# Rain_Sensor.net
KiCad netlist of a schematic drawn in EasyEDA Pro
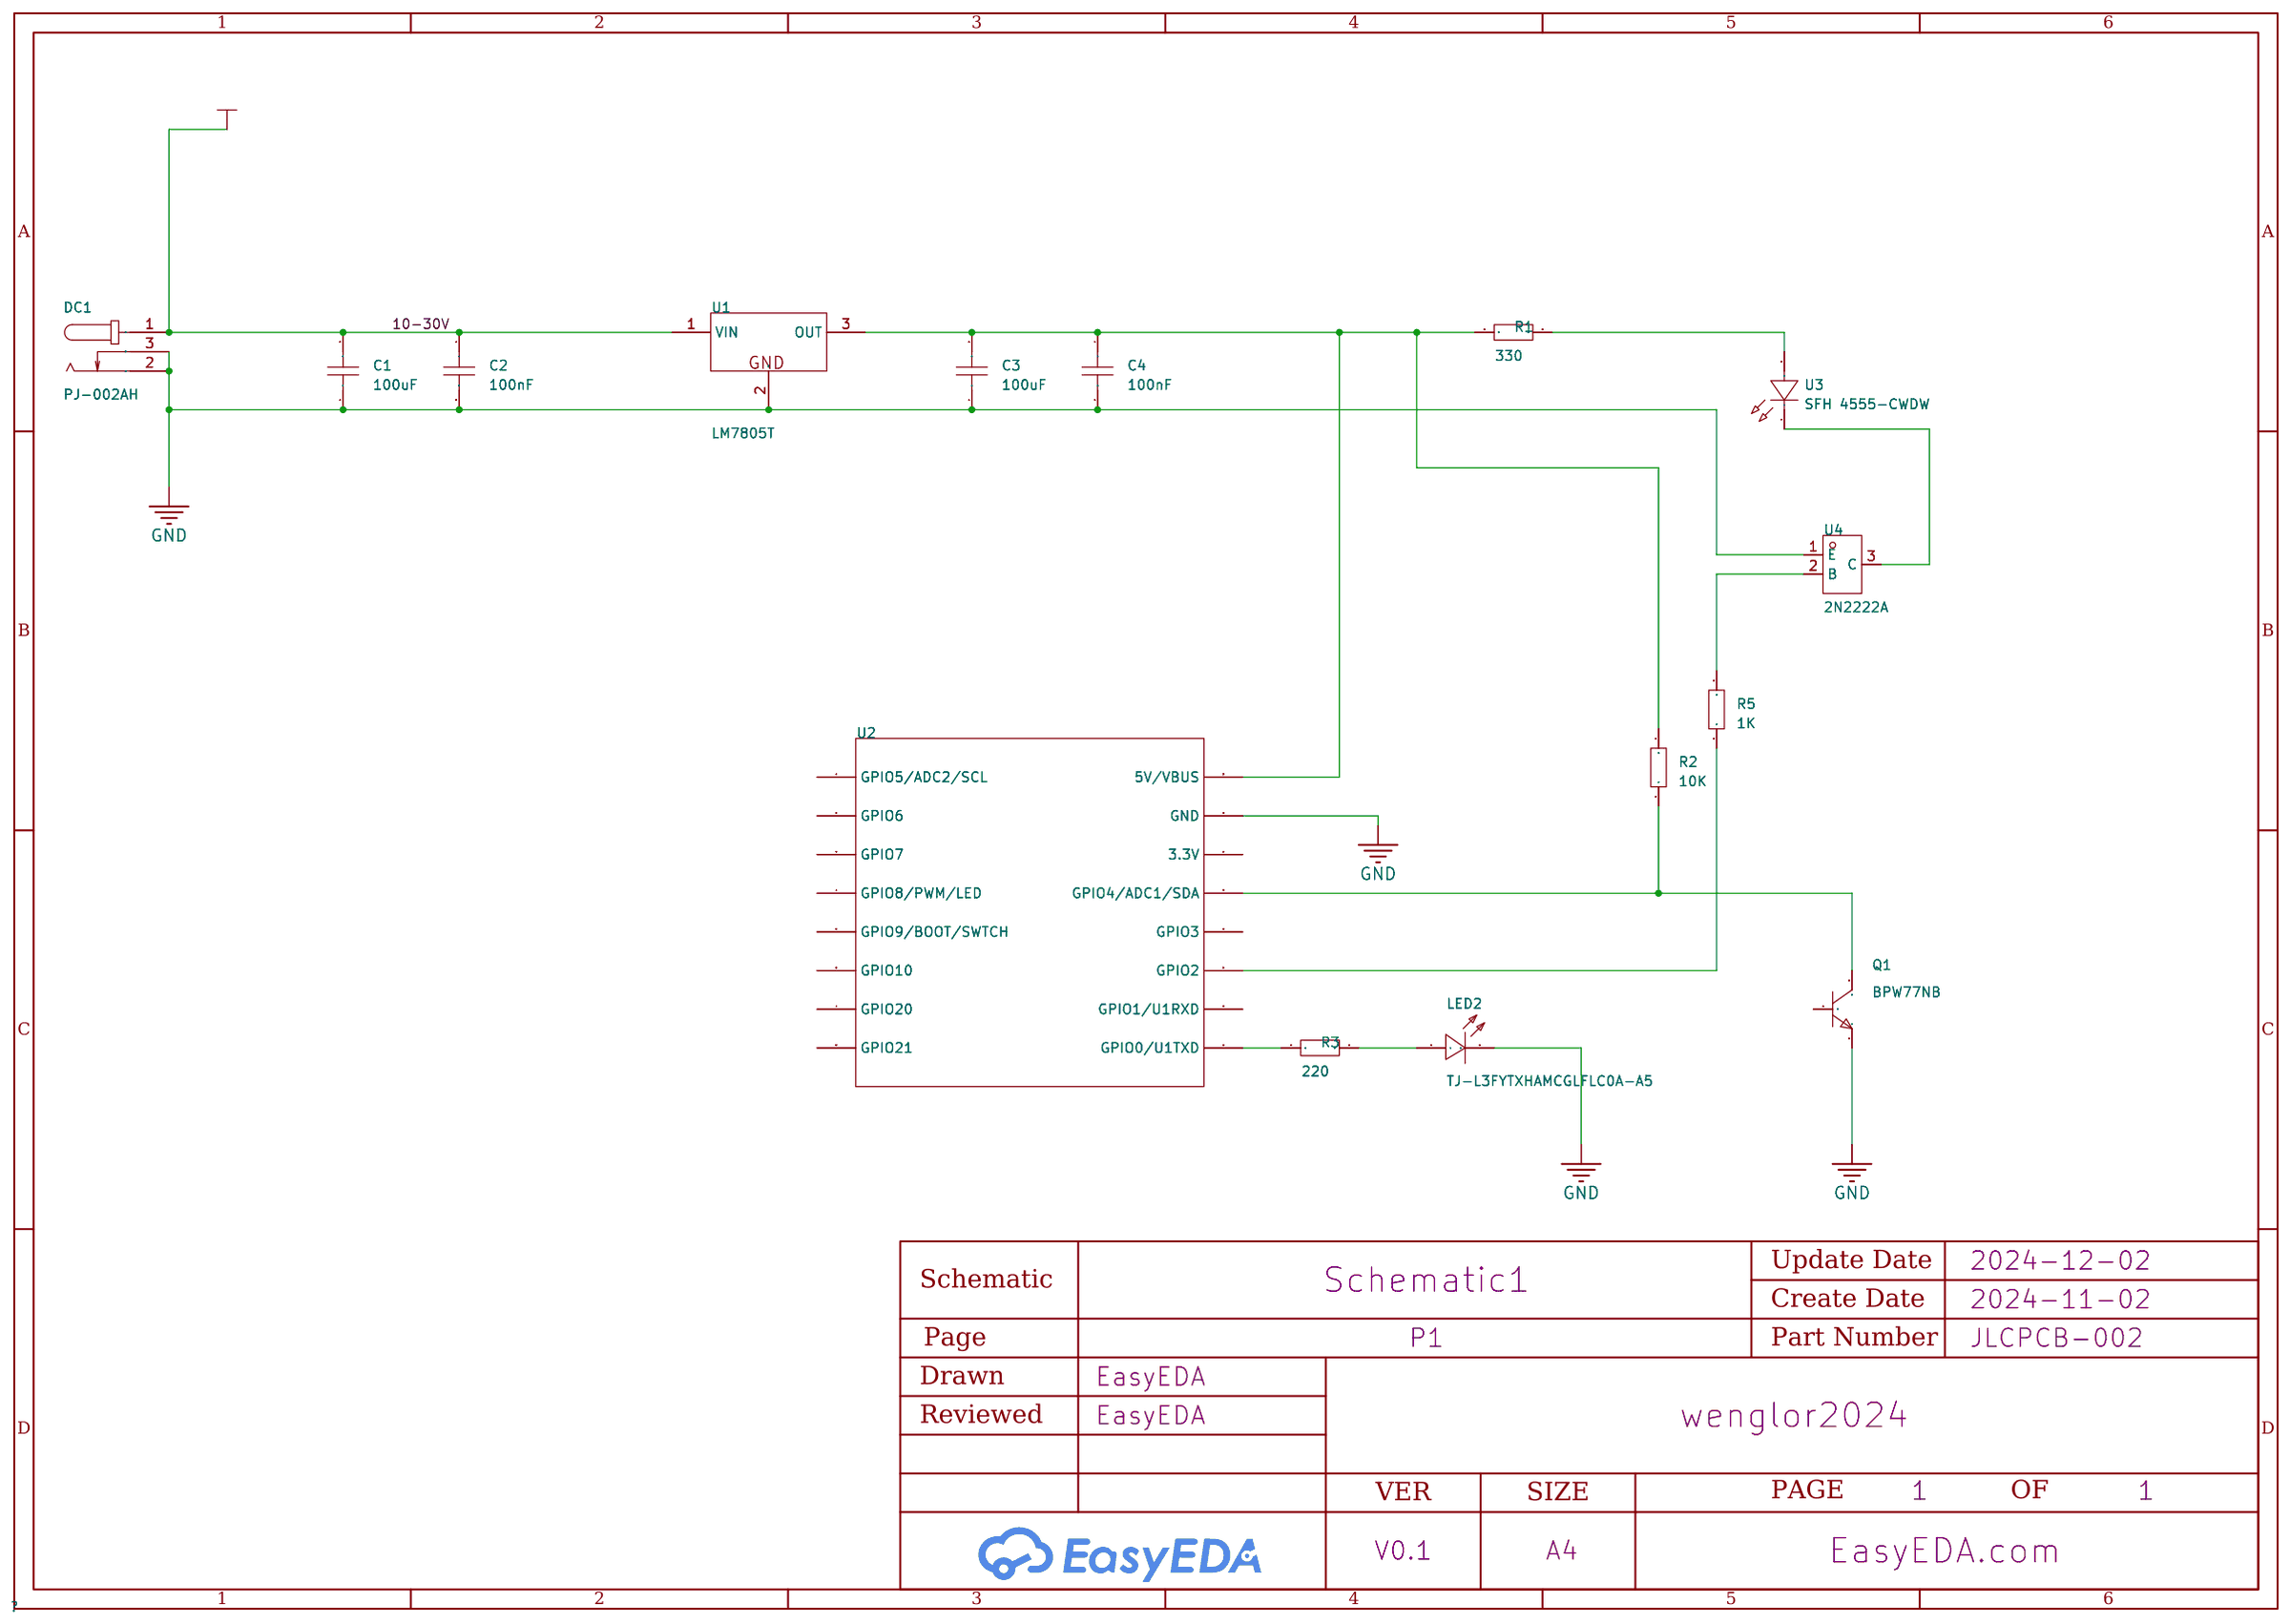
[diagram p0: schematic sheet]

(export (version "E")
  (design (tool "Eeschema 10.0.6"))
  (components
    (comp (ref "C1")
      (value "100uF")
      (footprint "easyedapro:C0603")
      (libsource (lib "easyedapro") (part "CAP"))
    )
    (comp (ref "C2")
      (value "100nF")
      (footprint "easyedapro:C0603")
      (libsource (lib "easyedapro") (part "CAP"))
    )
    (comp (ref "C3")
      (value "100uF")
      (footprint "easyedapro:C0603")
      (libsource (lib "easyedapro") (part "CAP"))
    )
    (comp (ref "C4")
      (value "100nF")
      (footprint "easyedapro:C0603")
      (libsource (lib "easyedapro") (part "CAP"))
    )
    (comp (ref "DC1")
      (value "PJ-002AH")
      (footprint "easyedapro:DC-IN-TH_PJ-002AH")
      (fields (field (name "Manufacturer") "CUI"))
      (libsource (lib "easyedapro") (part "PJ-002AH"))
    )
    (comp (ref "LED2")
      (value "TJ-L3FYTXHAMCGLFLC0A-A5")
      (footprint "easyedapro:LED-TH_BD3.0-P2.54-FD")
      (fields (field (name "Manufacturer") "TOGIALED(统佳)"))
      (libsource (lib "easyedapro") (part "TJ-L3FYTXHAMCGLFLC0A-A5"))
    )
    (comp (ref "Q1")
      (value "BPW77NB")
      (footprint "easyedapro:TO-18-3")
      (fields (field (name "Manufacturer") "VISHAY(威世)"))
      (libsource (lib "easyedapro") (part "BPW77NB"))
    )
    (comp (ref "R1") (value "330") (footprint "easyedapro:R0603") (libsource (lib "easyedapro") (part "Res")))
    (comp (ref "R2") (value "10K") (footprint "easyedapro:R0603") (libsource (lib "easyedapro") (part "Res")))
    (comp (ref "R3") (value "220") (footprint "easyedapro:R0603") (libsource (lib "easyedapro") (part "Res")))
    (comp (ref "R5") (value "1K") (footprint "easyedapro:R0603") (libsource (lib "easyedapro") (part "Res")))
    (comp (ref "U1")
      (value "LM7805T")
      (footprint "easyedapro:TO-220-3_L10.0-W4.5-P2.54-L")
      (description "Output Type:-")
      (fields (field (name "Manufacturer") "HGC(华冠)"))
      (libsource (lib "easyedapro") (part "LM7805T"))
    )
    (comp (ref "U2")
      (value "~")
      (footprint "easyedapro:ESP32-C3-SUPER-MINI")
      (libsource (lib "easyedapro") (part "ESP32-C3-SUPER-MINI"))
    )
    (comp (ref "U3")
      (value "SFH 4555-CWDW")
      (footprint "easyedapro:LED-TH_BD5.8-P2.54-RD")
      (fields (field (name "Manufacturer") "OSRAM(欧司朗)"))
      (libsource (lib "easyedapro") (part "SFH 4555-CWDW"))
    )
    (comp (ref "U4")
      (value "2N2222A")
      (footprint "easyedapro:TO-18-3_BD5.6_L14C1")
      (fields (field (name "Manufacturer") "MICROCHIP(美国微芯)"))
      (libsource (lib "easyedapro") (part "2N2222A_C3200770"))
    )
  )
  (nets
    (net (code "1") (name "10-30V") (class "Default")
      (node (ref "C1") (pin "2") (pinfunction "2_2") (pintype "input"))
      (node (ref "C2") (pin "1") (pinfunction "1_1") (pintype "input"))
      (node (ref "DC1") (pin "1") (pinfunction "1_1") (pintype "unspecified"))
      (node (ref "U1") (pin "1") (pinfunction "VIN_1") (pintype "input"))
    )
    (net (code "2") (name "GND") (class "Default")
      (node (ref "C1") (pin "1") (pinfunction "1_1") (pintype "input"))
      (node (ref "C2") (pin "2") (pinfunction "2_2") (pintype "input"))
      (node (ref "C3") (pin "1") (pinfunction "1_1") (pintype "input"))
      (node (ref "C4") (pin "2") (pinfunction "2_2") (pintype "input"))
      (node (ref "DC1") (pin "2") (pinfunction "2_2") (pintype "unspecified"))
      (node (ref "DC1") (pin "3") (pinfunction "3_3") (pintype "unspecified"))
      (node (ref "LED2") (pin "2") (pinfunction "C_2") (pintype "unspecified"))
      (node (ref "Q1") (pin "1") (pinfunction "E_1") (pintype "input"))
      (node (ref "U1") (pin "2") (pinfunction "GND_2") (pintype "input"))
      (node (ref "U2") (pin "15") (pinfunction "GND_15") (pintype "unspecified"))
      (node (ref "U4") (pin "1") (pinfunction "E_1") (pintype "unspecified"))
    )
    (net (code "3") (name "Net-(LED2-A)") (class "Default")
      (node (ref "LED2") (pin "1") (pinfunction "A_1") (pintype "unspecified"))
      (node (ref "R3") (pin "2") (pinfunction "2_2") (pintype "input"))
    )
    (net (code "4") (name "Net-(Q1-C)") (class "Default")
      (node (ref "Q1") (pin "3") (pinfunction "C_3") (pintype "input"))
      (node (ref "R2") (pin "1") (pinfunction "1_1") (pintype "input"))
      (node (ref "U2") (pin "13") (pinfunction "GPIO4/ADC1/SDA_13") (pintype "unspecified"))
    )
    (net (code "5") (name "Net-(U1-OUT)") (class "Default")
      (node (ref "C3") (pin "2") (pinfunction "2_2") (pintype "input"))
      (node (ref "C4") (pin "1") (pinfunction "1_1") (pintype "input"))
      (node (ref "R1") (pin "1") (pinfunction "1_1") (pintype "input"))
      (node (ref "R2") (pin "2") (pinfunction "2_2") (pintype "input"))
      (node (ref "U1") (pin "3") (pinfunction "OUT_3") (pintype "input"))
      (node (ref "U2") (pin "16") (pinfunction "5V/VBUS_16") (pintype "unspecified"))
    )
    (net (code "6") (name "Net-(U2-GPIO0{slash}U1TXD)") (class "Default")
      (node (ref "R3") (pin "1") (pinfunction "1_1") (pintype "input"))
      (node (ref "U2") (pin "9") (pinfunction "GPIO0/U1TXD_9") (pintype "unspecified"))
    )
    (net (code "7") (name "Net-(U2-GPIO2)") (class "Default")
      (node (ref "R5") (pin "1") (pinfunction "1_1") (pintype "input"))
      (node (ref "U2") (pin "11") (pinfunction "GPIO2_11") (pintype "unspecified"))
    )
    (net (code "8") (name "Net-(U3-A)") (class "Default")
      (node (ref "R1") (pin "2") (pinfunction "2_2") (pintype "input"))
      (node (ref "U3") (pin "2") (pinfunction "A_2") (pintype "unspecified"))
    )
    (net (code "9") (name "Net-(U3-K)") (class "Default")
      (node (ref "U3") (pin "1") (pinfunction "K_1") (pintype "unspecified"))
      (node (ref "U4") (pin "3") (pinfunction "C_3") (pintype "unspecified"))
    )
    (net (code "10") (name "Net-(U4-B)") (class "Default")
      (node (ref "R5") (pin "2") (pinfunction "2_2") (pintype "input"))
      (node (ref "U4") (pin "2") (pinfunction "B_2") (pintype "unspecified"))
    )
    (net (code "11") (name "unconnected-(Q1-B-Pad2)") (class "Default")
      (node (ref "Q1") (pin "2") (pinfunction "B_2") (pintype "input"))
    )
    (net (code "12") (name "unconnected-(U2-3.3V-Pad14)") (class "Default")
      (node (ref "U2") (pin "14") (pinfunction "3.3V_14") (pintype "unspecified"))
    )
    (net (code "13") (name "unconnected-(U2-GPIO1{slash}U1RXD-Pad10)") (class "Default")
      (node (ref "U2") (pin "10") (pinfunction "GPIO1/U1RXD_10") (pintype "unspecified"))
    )
    (net (code "14") (name "unconnected-(U2-GPIO3-Pad12)") (class "Default")
      (node (ref "U2") (pin "12") (pinfunction "GPIO3_12") (pintype "unspecified"))
    )
    (net (code "15") (name "unconnected-(U2-GPIO5{slash}ADC2{slash}SCL-Pad1)") (class "Default")
      (node (ref "U2") (pin "1") (pinfunction "GPIO5/ADC2/SCL_1") (pintype "unspecified"))
    )
    (net (code "16") (name "unconnected-(U2-GPIO6-Pad2)") (class "Default")
      (node (ref "U2") (pin "2") (pinfunction "GPIO6_2") (pintype "unspecified"))
    )
    (net (code "17") (name "unconnected-(U2-GPIO7-Pad3)") (class "Default")
      (node (ref "U2") (pin "3") (pinfunction "GPIO7_3") (pintype "unspecified"))
    )
    (net (code "18") (name "unconnected-(U2-GPIO8{slash}PWM{slash}LED-Pad4)") (class "Default")
      (node (ref "U2") (pin "4") (pinfunction "GPIO8/PWM/LED_4") (pintype "unspecified"))
    )
    (net (code "19") (name "unconnected-(U2-GPIO9{slash}BOOT{slash}SWTCH-Pad5)") (class "Default")
      (node (ref "U2") (pin "5") (pinfunction "GPIO9/BOOT/SWTCH_5") (pintype "unspecified"))
    )
    (net (code "20") (name "unconnected-(U2-GPIO10-Pad6)") (class "Default")
      (node (ref "U2") (pin "6") (pinfunction "GPIO10_6") (pintype "unspecified"))
    )
    (net (code "21") (name "unconnected-(U2-GPIO20-Pad7)") (class "Default")
      (node (ref "U2") (pin "7") (pinfunction "GPIO20_7") (pintype "unspecified"))
    )
    (net (code "22") (name "unconnected-(U2-GPIO21-Pad8)") (class "Default")
      (node (ref "U2") (pin "8") (pinfunction "GPIO21_8") (pintype "unspecified"))
    )
  )
)
